# B168X.net
KiCad netlist of a schematic drawn in EAGLE
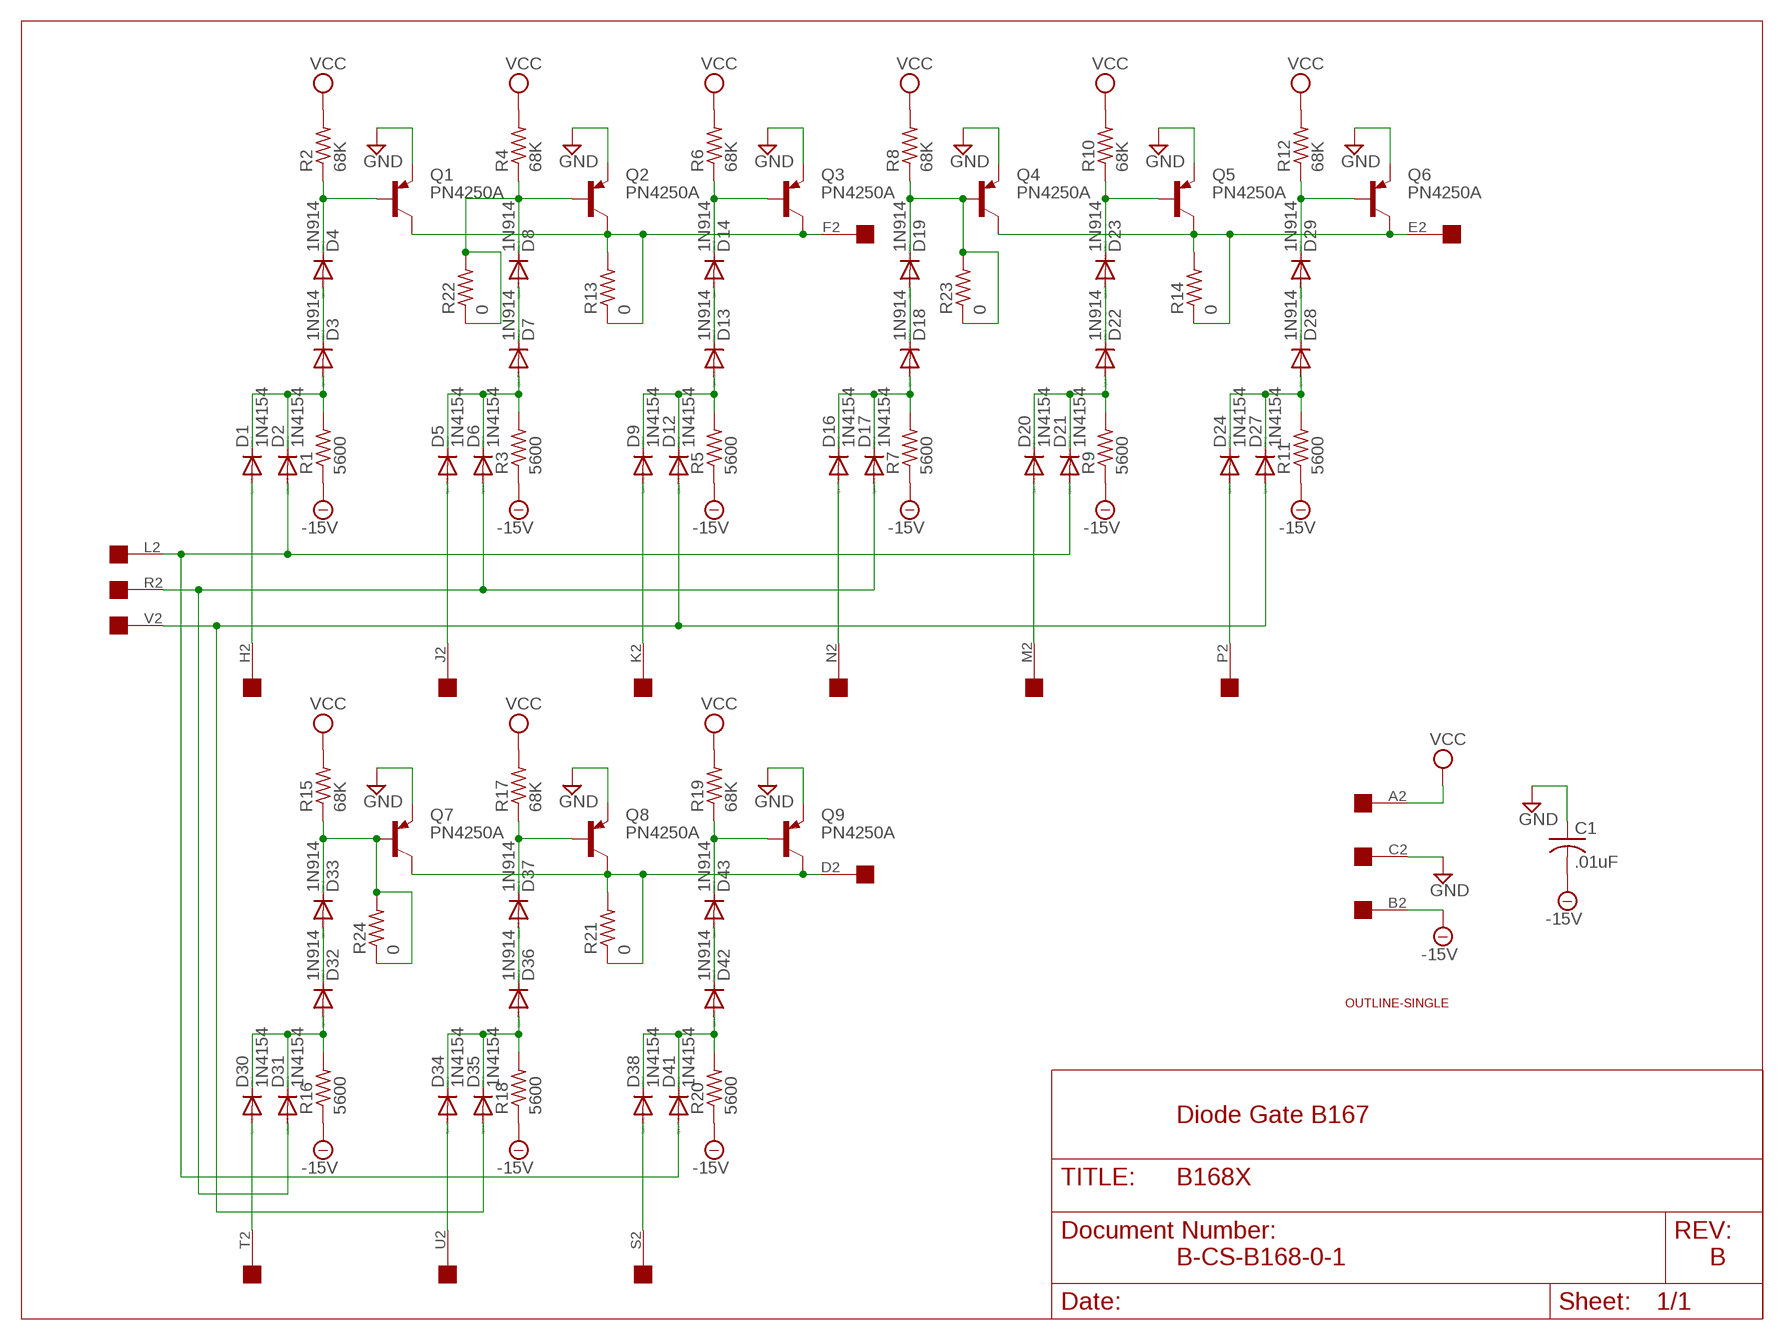
[diagram p0: schematic, sheet 1]

(export (version "E")
  (design (tool "Eeschema 10.0.6"))
  (components
    (comp (ref "C1")
      (value ".01uF")
      (footprint "eagle-import:C063-025X075")
      (libsource (lib "eagle-import") (part "C-US"))
    )
    (comp (ref "D1")
      (value "1N4154")
      (footprint "eagle-import:DO35-10")
      (libsource (lib "eagle-import") (part "DIODE-DO35-10"))
    )
    (comp (ref "D2")
      (value "1N4154")
      (footprint "eagle-import:DO35-10")
      (libsource (lib "eagle-import") (part "DIODE-DO35-10"))
    )
    (comp (ref "D3")
      (value "1N914")
      (footprint "eagle-import:DO35-10")
      (libsource (lib "eagle-import") (part "DIODE-DO35-10"))
    )
    (comp (ref "D4")
      (value "1N914")
      (footprint "eagle-import:DO35-10")
      (libsource (lib "eagle-import") (part "DIODE-DO35-10"))
    )
    (comp (ref "D5")
      (value "1N4154")
      (footprint "eagle-import:DO35-10")
      (libsource (lib "eagle-import") (part "DIODE-DO35-10"))
    )
    (comp (ref "D6")
      (value "1N4154")
      (footprint "eagle-import:DO35-10")
      (libsource (lib "eagle-import") (part "DIODE-DO35-10"))
    )
    (comp (ref "D7")
      (value "1N914")
      (footprint "eagle-import:DO35-10")
      (libsource (lib "eagle-import") (part "DIODE-DO35-10"))
    )
    (comp (ref "D8")
      (value "1N914")
      (footprint "eagle-import:DO35-10")
      (libsource (lib "eagle-import") (part "DIODE-DO35-10"))
    )
    (comp (ref "D9")
      (value "1N4154")
      (footprint "eagle-import:DO35-10")
      (libsource (lib "eagle-import") (part "DIODE-DO35-10"))
    )
    (comp (ref "D12")
      (value "1N4154")
      (footprint "eagle-import:DO35-10")
      (libsource (lib "eagle-import") (part "DIODE-DO35-10"))
    )
    (comp (ref "D13")
      (value "1N914")
      (footprint "eagle-import:DO35-10")
      (libsource (lib "eagle-import") (part "DIODE-DO35-10"))
    )
    (comp (ref "D14")
      (value "1N914")
      (footprint "eagle-import:DO35-10")
      (libsource (lib "eagle-import") (part "DIODE-DO35-10"))
    )
    (comp (ref "D16")
      (value "1N4154")
      (footprint "eagle-import:DO35-10")
      (libsource (lib "eagle-import") (part "DIODE-DO35-10"))
    )
    (comp (ref "D17")
      (value "1N4154")
      (footprint "eagle-import:DO35-10")
      (libsource (lib "eagle-import") (part "DIODE-DO35-10"))
    )
    (comp (ref "D18")
      (value "1N914")
      (footprint "eagle-import:DO35-10")
      (libsource (lib "eagle-import") (part "DIODE-DO35-10"))
    )
    (comp (ref "D19")
      (value "1N914")
      (footprint "eagle-import:DO35-10")
      (libsource (lib "eagle-import") (part "DIODE-DO35-10"))
    )
    (comp (ref "D20")
      (value "1N4154")
      (footprint "eagle-import:DO35-10")
      (libsource (lib "eagle-import") (part "DIODE-DO35-10"))
    )
    (comp (ref "D21")
      (value "1N4154")
      (footprint "eagle-import:DO35-10")
      (libsource (lib "eagle-import") (part "DIODE-DO35-10"))
    )
    (comp (ref "D22")
      (value "1N914")
      (footprint "eagle-import:DO35-10")
      (libsource (lib "eagle-import") (part "DIODE-DO35-10"))
    )
    (comp (ref "D23")
      (value "1N914")
      (footprint "eagle-import:DO35-10")
      (libsource (lib "eagle-import") (part "DIODE-DO35-10"))
    )
    (comp (ref "D24")
      (value "1N4154")
      (footprint "eagle-import:DO35-10")
      (libsource (lib "eagle-import") (part "DIODE-DO35-10"))
    )
    (comp (ref "D27")
      (value "1N4154")
      (footprint "eagle-import:DO35-10")
      (libsource (lib "eagle-import") (part "DIODE-DO35-10"))
    )
    (comp (ref "D28")
      (value "1N914")
      (footprint "eagle-import:DO35-10")
      (libsource (lib "eagle-import") (part "DIODE-DO35-10"))
    )
    (comp (ref "D29")
      (value "1N914")
      (footprint "eagle-import:DO35-10")
      (libsource (lib "eagle-import") (part "DIODE-DO35-10"))
    )
    (comp (ref "D30")
      (value "1N4154")
      (footprint "eagle-import:DO35-10")
      (libsource (lib "eagle-import") (part "DIODE-DO35-10"))
    )
    (comp (ref "D31")
      (value "1N4154")
      (footprint "eagle-import:DO35-10")
      (libsource (lib "eagle-import") (part "DIODE-DO35-10"))
    )
    (comp (ref "D32")
      (value "1N914")
      (footprint "eagle-import:DO35-10")
      (libsource (lib "eagle-import") (part "DIODE-DO35-10"))
    )
    (comp (ref "D33")
      (value "1N914")
      (footprint "eagle-import:DO35-10")
      (libsource (lib "eagle-import") (part "DIODE-DO35-10"))
    )
    (comp (ref "D34")
      (value "1N4154")
      (footprint "eagle-import:DO35-10")
      (libsource (lib "eagle-import") (part "DIODE-DO35-10"))
    )
    (comp (ref "D35")
      (value "1N4154")
      (footprint "eagle-import:DO35-10")
      (libsource (lib "eagle-import") (part "DIODE-DO35-10"))
    )
    (comp (ref "D36")
      (value "1N914")
      (footprint "eagle-import:DO35-10")
      (libsource (lib "eagle-import") (part "DIODE-DO35-10"))
    )
    (comp (ref "D37")
      (value "1N914")
      (footprint "eagle-import:DO35-10")
      (libsource (lib "eagle-import") (part "DIODE-DO35-10"))
    )
    (comp (ref "D38")
      (value "1N4154")
      (footprint "eagle-import:DO35-10")
      (libsource (lib "eagle-import") (part "DIODE-DO35-10"))
    )
    (comp (ref "D41")
      (value "1N4154")
      (footprint "eagle-import:DO35-10")
      (libsource (lib "eagle-import") (part "DIODE-DO35-10"))
    )
    (comp (ref "D42")
      (value "1N914")
      (footprint "eagle-import:DO35-10")
      (libsource (lib "eagle-import") (part "DIODE-DO35-10"))
    )
    (comp (ref "D43")
      (value "1N914")
      (footprint "eagle-import:DO35-10")
      (libsource (lib "eagle-import") (part "DIODE-DO35-10"))
    )
    (comp (ref "Q1")
      (value "PN4250A")
      (footprint "eagle-import:TO5")
      (libsource (lib "eagle-import") (part "-PNP-TO5"))
    )
    (comp (ref "Q2")
      (value "PN4250A")
      (footprint "eagle-import:TO5")
      (libsource (lib "eagle-import") (part "-PNP-TO5"))
    )
    (comp (ref "Q3")
      (value "PN4250A")
      (footprint "eagle-import:TO5")
      (libsource (lib "eagle-import") (part "-PNP-TO5"))
    )
    (comp (ref "Q4")
      (value "PN4250A")
      (footprint "eagle-import:TO5")
      (libsource (lib "eagle-import") (part "-PNP-TO5"))
    )
    (comp (ref "Q5")
      (value "PN4250A")
      (footprint "eagle-import:TO5")
      (libsource (lib "eagle-import") (part "-PNP-TO5"))
    )
    (comp (ref "Q6")
      (value "PN4250A")
      (footprint "eagle-import:TO5")
      (libsource (lib "eagle-import") (part "-PNP-TO5"))
    )
    (comp (ref "Q7")
      (value "PN4250A")
      (footprint "eagle-import:TO5")
      (libsource (lib "eagle-import") (part "-PNP-TO5"))
    )
    (comp (ref "Q8")
      (value "PN4250A")
      (footprint "eagle-import:TO5")
      (libsource (lib "eagle-import") (part "-PNP-TO5"))
    )
    (comp (ref "Q9")
      (value "PN4250A")
      (footprint "eagle-import:TO5")
      (libsource (lib "eagle-import") (part "-PNP-TO5"))
    )
    (comp (ref "R1")
      (value "5600")
      (footprint "eagle-import:0207_10")
      (libsource (lib "eagle-import") (part "R-US_0207/10"))
    )
    (comp (ref "R2")
      (value "68K")
      (footprint "eagle-import:0207_10")
      (libsource (lib "eagle-import") (part "R-US_0207/10"))
    )
    (comp (ref "R3")
      (value "5600")
      (footprint "eagle-import:0207_10")
      (libsource (lib "eagle-import") (part "R-US_0207/10"))
    )
    (comp (ref "R4")
      (value "68K")
      (footprint "eagle-import:0207_10")
      (libsource (lib "eagle-import") (part "R-US_0207/10"))
    )
    (comp (ref "R5")
      (value "5600")
      (footprint "eagle-import:0207_10")
      (libsource (lib "eagle-import") (part "R-US_0207/10"))
    )
    (comp (ref "R6")
      (value "68K")
      (footprint "eagle-import:0207_10")
      (libsource (lib "eagle-import") (part "R-US_0207/10"))
    )
    (comp (ref "R7")
      (value "5600")
      (footprint "eagle-import:0207_10")
      (libsource (lib "eagle-import") (part "R-US_0207/10"))
    )
    (comp (ref "R8")
      (value "68K")
      (footprint "eagle-import:0207_10")
      (libsource (lib "eagle-import") (part "R-US_0207/10"))
    )
    (comp (ref "R9")
      (value "5600")
      (footprint "eagle-import:0207_10")
      (libsource (lib "eagle-import") (part "R-US_0207/10"))
    )
    (comp (ref "R10")
      (value "68K")
      (footprint "eagle-import:0207_10")
      (libsource (lib "eagle-import") (part "R-US_0207/10"))
    )
    (comp (ref "R11")
      (value "5600")
      (footprint "eagle-import:0207_10")
      (libsource (lib "eagle-import") (part "R-US_0207/10"))
    )
    (comp (ref "R12")
      (value "68K")
      (footprint "eagle-import:0207_10")
      (libsource (lib "eagle-import") (part "R-US_0207/10"))
    )
    (comp (ref "R13")
      (value "0")
      (footprint "eagle-import:0207_10")
      (libsource (lib "eagle-import") (part "R-US_0207/10"))
    )
    (comp (ref "R14")
      (value "0")
      (footprint "eagle-import:0207_10")
      (libsource (lib "eagle-import") (part "R-US_0207/10"))
    )
    (comp (ref "R15")
      (value "68K")
      (footprint "eagle-import:0207_10")
      (libsource (lib "eagle-import") (part "R-US_0207/10"))
    )
    (comp (ref "R16")
      (value "5600")
      (footprint "eagle-import:0207_10")
      (libsource (lib "eagle-import") (part "R-US_0207/10"))
    )
    (comp (ref "R17")
      (value "68K")
      (footprint "eagle-import:0207_10")
      (libsource (lib "eagle-import") (part "R-US_0207/10"))
    )
    (comp (ref "R18")
      (value "5600")
      (footprint "eagle-import:0207_10")
      (libsource (lib "eagle-import") (part "R-US_0207/10"))
    )
    (comp (ref "R19")
      (value "68K")
      (footprint "eagle-import:0207_10")
      (libsource (lib "eagle-import") (part "R-US_0207/10"))
    )
    (comp (ref "R20")
      (value "5600")
      (footprint "eagle-import:0207_10")
      (libsource (lib "eagle-import") (part "R-US_0207/10"))
    )
    (comp (ref "R21")
      (value "0")
      (footprint "eagle-import:0207_10")
      (libsource (lib "eagle-import") (part "R-US_0207/10"))
    )
    (comp (ref "R22")
      (value "0")
      (footprint "eagle-import:0207_10")
      (libsource (lib "eagle-import") (part "R-US_0207/10"))
    )
    (comp (ref "R23")
      (value "0")
      (footprint "eagle-import:0207_10")
      (libsource (lib "eagle-import") (part "R-US_0207/10"))
    )
    (comp (ref "R24")
      (value "0")
      (footprint "eagle-import:0207_10")
      (libsource (lib "eagle-import") (part "R-US_0207/10"))
    )
    (comp (ref "U$1")
      (value "OUTLINE-SINGLE")
      (footprint "eagle-import:SINGLE")
      (libsource (lib "eagle-import") (part "OUTLINE-SINGLE"))
    )
    (comp (ref "U$2")
      (value "EDGE-1")
      (footprint "eagle-import:EDGE-CON1")
      (libsource (lib "eagle-import") (part "EDGE-1"))
    )
  )
  (nets
    (net (code "1") (name "-15V") (class "Default")
      (node (ref "C1") (pin "2") (pinfunction "2_2") (pintype "passive"))
      (node (ref "R1") (pin "1") (pinfunction "1_1") (pintype "passive"))
      (node (ref "R11") (pin "1") (pinfunction "1_1") (pintype "passive"))
      (node (ref "R16") (pin "1") (pinfunction "1_1") (pintype "passive"))
      (node (ref "R18") (pin "1") (pinfunction "1_1") (pintype "passive"))
      (node (ref "R20") (pin "1") (pinfunction "1_1") (pintype "passive"))
      (node (ref "R3") (pin "1") (pinfunction "1_1") (pintype "passive"))
      (node (ref "R5") (pin "1") (pinfunction "1_1") (pintype "passive"))
      (node (ref "R7") (pin "1") (pinfunction "1_1") (pintype "passive"))
      (node (ref "R9") (pin "1") (pinfunction "1_1") (pintype "passive"))
      (node (ref "U$2") (pin "B2") (pinfunction "1_B2") (pintype "bidirectional"))
    )
    (net (code "2") (name "GND") (class "Default")
      (node (ref "C1") (pin "1") (pinfunction "1_1") (pintype "passive"))
      (node (ref "Q1") (pin "1") (pinfunction "E_1") (pintype "passive"))
      (node (ref "Q2") (pin "1") (pinfunction "E_1") (pintype "passive"))
      (node (ref "Q3") (pin "1") (pinfunction "E_1") (pintype "passive"))
      (node (ref "Q4") (pin "1") (pinfunction "E_1") (pintype "passive"))
      (node (ref "Q5") (pin "1") (pinfunction "E_1") (pintype "passive"))
      (node (ref "Q6") (pin "1") (pinfunction "E_1") (pintype "passive"))
      (node (ref "Q7") (pin "1") (pinfunction "E_1") (pintype "passive"))
      (node (ref "Q8") (pin "1") (pinfunction "E_1") (pintype "passive"))
      (node (ref "Q9") (pin "1") (pinfunction "E_1") (pintype "passive"))
      (node (ref "U$2") (pin "C2") (pinfunction "1_C2") (pintype "bidirectional"))
    )
    (net (code "3") (name "Net-(D1-PadC)") (class "Default")
      (node (ref "D1") (pin "C") (pinfunction "C_C") (pintype "passive"))
      (node (ref "D2") (pin "C") (pinfunction "C_C") (pintype "passive"))
      (node (ref "D3") (pin "A") (pinfunction "A_A") (pintype "passive"))
      (node (ref "R1") (pin "2") (pinfunction "2_2") (pintype "passive"))
    )
    (net (code "4") (name "Net-(D3-PadC)") (class "Default")
      (node (ref "D3") (pin "C") (pinfunction "C_C") (pintype "passive"))
      (node (ref "D4") (pin "A") (pinfunction "A_A") (pintype "passive"))
    )
    (net (code "5") (name "Net-(D5-PadC)") (class "Default")
      (node (ref "D5") (pin "C") (pinfunction "C_C") (pintype "passive"))
      (node (ref "D6") (pin "C") (pinfunction "C_C") (pintype "passive"))
      (node (ref "D7") (pin "A") (pinfunction "A_A") (pintype "passive"))
      (node (ref "R3") (pin "2") (pinfunction "2_2") (pintype "passive"))
    )
    (net (code "6") (name "Net-(D7-PadC)") (class "Default")
      (node (ref "D7") (pin "C") (pinfunction "C_C") (pintype "passive"))
      (node (ref "D8") (pin "A") (pinfunction "A_A") (pintype "passive"))
    )
    (net (code "7") (name "Net-(D12-PadC)") (class "Default")
      (node (ref "D12") (pin "C") (pinfunction "C_C") (pintype "passive"))
      (node (ref "D13") (pin "A") (pinfunction "A_A") (pintype "passive"))
      (node (ref "D9") (pin "C") (pinfunction "C_C") (pintype "passive"))
      (node (ref "R5") (pin "2") (pinfunction "2_2") (pintype "passive"))
    )
    (net (code "8") (name "Net-(D13-PadC)") (class "Default")
      (node (ref "D13") (pin "C") (pinfunction "C_C") (pintype "passive"))
      (node (ref "D14") (pin "A") (pinfunction "A_A") (pintype "passive"))
    )
    (net (code "9") (name "Net-(D16-PadC)") (class "Default")
      (node (ref "D16") (pin "C") (pinfunction "C_C") (pintype "passive"))
      (node (ref "D17") (pin "C") (pinfunction "C_C") (pintype "passive"))
      (node (ref "D18") (pin "A") (pinfunction "A_A") (pintype "passive"))
      (node (ref "R7") (pin "2") (pinfunction "2_2") (pintype "passive"))
    )
    (net (code "10") (name "Net-(D18-PadC)") (class "Default")
      (node (ref "D18") (pin "C") (pinfunction "C_C") (pintype "passive"))
      (node (ref "D19") (pin "A") (pinfunction "A_A") (pintype "passive"))
    )
    (net (code "11") (name "Net-(D20-PadC)") (class "Default")
      (node (ref "D20") (pin "C") (pinfunction "C_C") (pintype "passive"))
      (node (ref "D21") (pin "C") (pinfunction "C_C") (pintype "passive"))
      (node (ref "D22") (pin "A") (pinfunction "A_A") (pintype "passive"))
      (node (ref "R9") (pin "2") (pinfunction "2_2") (pintype "passive"))
    )
    (net (code "12") (name "Net-(D22-PadC)") (class "Default")
      (node (ref "D22") (pin "C") (pinfunction "C_C") (pintype "passive"))
      (node (ref "D23") (pin "A") (pinfunction "A_A") (pintype "passive"))
    )
    (net (code "13") (name "Net-(D24-PadC)") (class "Default")
      (node (ref "D24") (pin "C") (pinfunction "C_C") (pintype "passive"))
      (node (ref "D27") (pin "C") (pinfunction "C_C") (pintype "passive"))
      (node (ref "D28") (pin "A") (pinfunction "A_A") (pintype "passive"))
      (node (ref "R11") (pin "2") (pinfunction "2_2") (pintype "passive"))
    )
    (net (code "14") (name "Net-(D28-PadC)") (class "Default")
      (node (ref "D28") (pin "C") (pinfunction "C_C") (pintype "passive"))
      (node (ref "D29") (pin "A") (pinfunction "A_A") (pintype "passive"))
    )
    (net (code "15") (name "Net-(D30-PadC)") (class "Default")
      (node (ref "D30") (pin "C") (pinfunction "C_C") (pintype "passive"))
      (node (ref "D31") (pin "C") (pinfunction "C_C") (pintype "passive"))
      (node (ref "D32") (pin "A") (pinfunction "A_A") (pintype "passive"))
      (node (ref "R16") (pin "2") (pinfunction "2_2") (pintype "passive"))
    )
    (net (code "16") (name "Net-(D32-PadC)") (class "Default")
      (node (ref "D32") (pin "C") (pinfunction "C_C") (pintype "passive"))
      (node (ref "D33") (pin "A") (pinfunction "A_A") (pintype "passive"))
    )
    (net (code "17") (name "Net-(D34-PadC)") (class "Default")
      (node (ref "D34") (pin "C") (pinfunction "C_C") (pintype "passive"))
      (node (ref "D35") (pin "C") (pinfunction "C_C") (pintype "passive"))
      (node (ref "D36") (pin "A") (pinfunction "A_A") (pintype "passive"))
      (node (ref "R18") (pin "2") (pinfunction "2_2") (pintype "passive"))
    )
    (net (code "18") (name "Net-(D36-PadC)") (class "Default")
      (node (ref "D36") (pin "C") (pinfunction "C_C") (pintype "passive"))
      (node (ref "D37") (pin "A") (pinfunction "A_A") (pintype "passive"))
    )
    (net (code "19") (name "Net-(D38-PadC)") (class "Default")
      (node (ref "D38") (pin "C") (pinfunction "C_C") (pintype "passive"))
      (node (ref "D41") (pin "C") (pinfunction "C_C") (pintype "passive"))
      (node (ref "D42") (pin "A") (pinfunction "A_A") (pintype "passive"))
      (node (ref "R20") (pin "2") (pinfunction "2_2") (pintype "passive"))
    )
    (net (code "20") (name "Net-(D42-PadC)") (class "Default")
      (node (ref "D42") (pin "C") (pinfunction "C_C") (pintype "passive"))
      (node (ref "D43") (pin "A") (pinfunction "A_A") (pintype "passive"))
    )
    (net (code "21") (name "Net-(Q1-B)") (class "Default")
      (node (ref "D4") (pin "C") (pinfunction "C_C") (pintype "passive"))
      (node (ref "Q1") (pin "2") (pinfunction "B_2") (pintype "passive"))
      (node (ref "R2") (pin "1") (pinfunction "1_1") (pintype "passive"))
    )
    (net (code "22") (name "Net-(Q1-C)") (class "Default")
      (node (ref "Q1") (pin "3") (pinfunction "C_3") (pintype "passive"))
      (node (ref "Q2") (pin "3") (pinfunction "C_3") (pintype "passive"))
      (node (ref "Q3") (pin "3") (pinfunction "C_3") (pintype "passive"))
      (node (ref "R13") (pin "1") (pinfunction "1_1") (pintype "passive"))
      (node (ref "R13") (pin "2") (pinfunction "2_2") (pintype "passive"))
      (node (ref "U$2") (pin "F2") (pinfunction "1_F2") (pintype "bidirectional"))
    )
    (net (code "23") (name "Net-(Q2-B)") (class "Default")
      (node (ref "D8") (pin "C") (pinfunction "C_C") (pintype "passive"))
      (node (ref "Q2") (pin "2") (pinfunction "B_2") (pintype "passive"))
      (node (ref "R22") (pin "1") (pinfunction "1_1") (pintype "passive"))
      (node (ref "R22") (pin "2") (pinfunction "2_2") (pintype "passive"))
      (node (ref "R4") (pin "1") (pinfunction "1_1") (pintype "passive"))
    )
    (net (code "24") (name "Net-(Q3-B)") (class "Default")
      (node (ref "D14") (pin "C") (pinfunction "C_C") (pintype "passive"))
      (node (ref "Q3") (pin "2") (pinfunction "B_2") (pintype "passive"))
      (node (ref "R6") (pin "1") (pinfunction "1_1") (pintype "passive"))
    )
    (net (code "25") (name "Net-(Q4-B)") (class "Default")
      (node (ref "D19") (pin "C") (pinfunction "C_C") (pintype "passive"))
      (node (ref "Q4") (pin "2") (pinfunction "B_2") (pintype "passive"))
      (node (ref "R23") (pin "1") (pinfunction "1_1") (pintype "passive"))
      (node (ref "R23") (pin "2") (pinfunction "2_2") (pintype "passive"))
      (node (ref "R8") (pin "1") (pinfunction "1_1") (pintype "passive"))
    )
    (net (code "26") (name "Net-(Q4-C)") (class "Default")
      (node (ref "Q4") (pin "3") (pinfunction "C_3") (pintype "passive"))
      (node (ref "Q5") (pin "3") (pinfunction "C_3") (pintype "passive"))
      (node (ref "Q6") (pin "3") (pinfunction "C_3") (pintype "passive"))
      (node (ref "R14") (pin "1") (pinfunction "1_1") (pintype "passive"))
      (node (ref "R14") (pin "2") (pinfunction "2_2") (pintype "passive"))
      (node (ref "U$2") (pin "E2") (pinfunction "1_E2") (pintype "bidirectional"))
    )
    (net (code "27") (name "Net-(Q5-B)") (class "Default")
      (node (ref "D23") (pin "C") (pinfunction "C_C") (pintype "passive"))
      (node (ref "Q5") (pin "2") (pinfunction "B_2") (pintype "passive"))
      (node (ref "R10") (pin "1") (pinfunction "1_1") (pintype "passive"))
    )
    (net (code "28") (name "Net-(Q6-B)") (class "Default")
      (node (ref "D29") (pin "C") (pinfunction "C_C") (pintype "passive"))
      (node (ref "Q6") (pin "2") (pinfunction "B_2") (pintype "passive"))
      (node (ref "R12") (pin "1") (pinfunction "1_1") (pintype "passive"))
    )
    (net (code "29") (name "Net-(Q7-B)") (class "Default")
      (node (ref "D33") (pin "C") (pinfunction "C_C") (pintype "passive"))
      (node (ref "Q7") (pin "2") (pinfunction "B_2") (pintype "passive"))
      (node (ref "R15") (pin "1") (pinfunction "1_1") (pintype "passive"))
      (node (ref "R24") (pin "1") (pinfunction "1_1") (pintype "passive"))
      (node (ref "R24") (pin "2") (pinfunction "2_2") (pintype "passive"))
    )
    (net (code "30") (name "Net-(Q7-C)") (class "Default")
      (node (ref "Q7") (pin "3") (pinfunction "C_3") (pintype "passive"))
      (node (ref "Q8") (pin "3") (pinfunction "C_3") (pintype "passive"))
      (node (ref "Q9") (pin "3") (pinfunction "C_3") (pintype "passive"))
      (node (ref "R21") (pin "1") (pinfunction "1_1") (pintype "passive"))
      (node (ref "R21") (pin "2") (pinfunction "2_2") (pintype "passive"))
      (node (ref "U$2") (pin "D2") (pinfunction "1_D2") (pintype "bidirectional"))
    )
    (net (code "31") (name "Net-(Q8-B)") (class "Default")
      (node (ref "D37") (pin "C") (pinfunction "C_C") (pintype "passive"))
      (node (ref "Q8") (pin "2") (pinfunction "B_2") (pintype "passive"))
      (node (ref "R17") (pin "1") (pinfunction "1_1") (pintype "passive"))
    )
    (net (code "32") (name "Net-(Q9-B)") (class "Default")
      (node (ref "D43") (pin "C") (pinfunction "C_C") (pintype "passive"))
      (node (ref "Q9") (pin "2") (pinfunction "B_2") (pintype "passive"))
      (node (ref "R19") (pin "1") (pinfunction "1_1") (pintype "passive"))
    )
    (net (code "33") (name "Net-(U$2G-1)") (class "Default")
      (node (ref "D1") (pin "A") (pinfunction "A_A") (pintype "passive"))
      (node (ref "U$2") (pin "H2") (pinfunction "1_H2") (pintype "bidirectional"))
    )
    (net (code "34") (name "Net-(U$2H-1)") (class "Default")
      (node (ref "D5") (pin "A") (pinfunction "A_A") (pintype "passive"))
      (node (ref "U$2") (pin "J2") (pinfunction "1_J2") (pintype "bidirectional"))
    )
    (net (code "35") (name "Net-(U$2I-1)") (class "Default")
      (node (ref "D9") (pin "A") (pinfunction "A_A") (pintype "passive"))
      (node (ref "U$2") (pin "K2") (pinfunction "1_K2") (pintype "bidirectional"))
    )
    (net (code "36") (name "Net-(U$2J-1)") (class "Default")
      (node (ref "D2") (pin "A") (pinfunction "A_A") (pintype "passive"))
      (node (ref "D21") (pin "A") (pinfunction "A_A") (pintype "passive"))
      (node (ref "D41") (pin "A") (pinfunction "A_A") (pintype "passive"))
      (node (ref "U$2") (pin "L2") (pinfunction "1_L2") (pintype "bidirectional"))
    )
    (net (code "37") (name "Net-(U$2K-1)") (class "Default")
      (node (ref "D20") (pin "A") (pinfunction "A_A") (pintype "passive"))
      (node (ref "U$2") (pin "M2") (pinfunction "1_M2") (pintype "bidirectional"))
    )
    (net (code "38") (name "Net-(U$2L-1)") (class "Default")
      (node (ref "D16") (pin "A") (pinfunction "A_A") (pintype "passive"))
      (node (ref "U$2") (pin "N2") (pinfunction "1_N2") (pintype "bidirectional"))
    )
    (net (code "39") (name "Net-(U$2M-1)") (class "Default")
      (node (ref "D24") (pin "A") (pinfunction "A_A") (pintype "passive"))
      (node (ref "U$2") (pin "P2") (pinfunction "1_P2") (pintype "bidirectional"))
    )
    (net (code "40") (name "Net-(U$2N-1)") (class "Default")
      (node (ref "D17") (pin "A") (pinfunction "A_A") (pintype "passive"))
      (node (ref "D31") (pin "A") (pinfunction "A_A") (pintype "passive"))
      (node (ref "D6") (pin "A") (pinfunction "A_A") (pintype "passive"))
      (node (ref "U$2") (pin "R2") (pinfunction "1_R2") (pintype "bidirectional"))
    )
    (net (code "41") (name "Net-(U$2O-1)") (class "Default")
      (node (ref "D38") (pin "A") (pinfunction "A_A") (pintype "passive"))
      (node (ref "U$2") (pin "S2") (pinfunction "1_S2") (pintype "bidirectional"))
    )
    (net (code "42") (name "Net-(U$2P-1)") (class "Default")
      (node (ref "D30") (pin "A") (pinfunction "A_A") (pintype "passive"))
      (node (ref "U$2") (pin "T2") (pinfunction "1_T2") (pintype "bidirectional"))
    )
    (net (code "43") (name "Net-(U$2Q-1)") (class "Default")
      (node (ref "D34") (pin "A") (pinfunction "A_A") (pintype "passive"))
      (node (ref "U$2") (pin "U2") (pinfunction "1_U2") (pintype "bidirectional"))
    )
    (net (code "44") (name "Net-(U$2R-1)") (class "Default")
      (node (ref "D12") (pin "A") (pinfunction "A_A") (pintype "passive"))
      (node (ref "D27") (pin "A") (pinfunction "A_A") (pintype "passive"))
      (node (ref "D35") (pin "A") (pinfunction "A_A") (pintype "passive"))
      (node (ref "U$2") (pin "V2") (pinfunction "1_V2") (pintype "bidirectional"))
    )
    (net (code "45") (name "VCC") (class "Default")
      (node (ref "R10") (pin "2") (pinfunction "2_2") (pintype "passive"))
      (node (ref "R12") (pin "2") (pinfunction "2_2") (pintype "passive"))
      (node (ref "R15") (pin "2") (pinfunction "2_2") (pintype "passive"))
      (node (ref "R17") (pin "2") (pinfunction "2_2") (pintype "passive"))
      (node (ref "R19") (pin "2") (pinfunction "2_2") (pintype "passive"))
      (node (ref "R2") (pin "2") (pinfunction "2_2") (pintype "passive"))
      (node (ref "R4") (pin "2") (pinfunction "2_2") (pintype "passive"))
      (node (ref "R6") (pin "2") (pinfunction "2_2") (pintype "passive"))
      (node (ref "R8") (pin "2") (pinfunction "2_2") (pintype "passive"))
      (node (ref "U$2") (pin "A2") (pinfunction "1_A2") (pintype "bidirectional"))
    )
  )
)
